# DCDC.net
KiCad netlist of a schematic drawn in Altium Designer
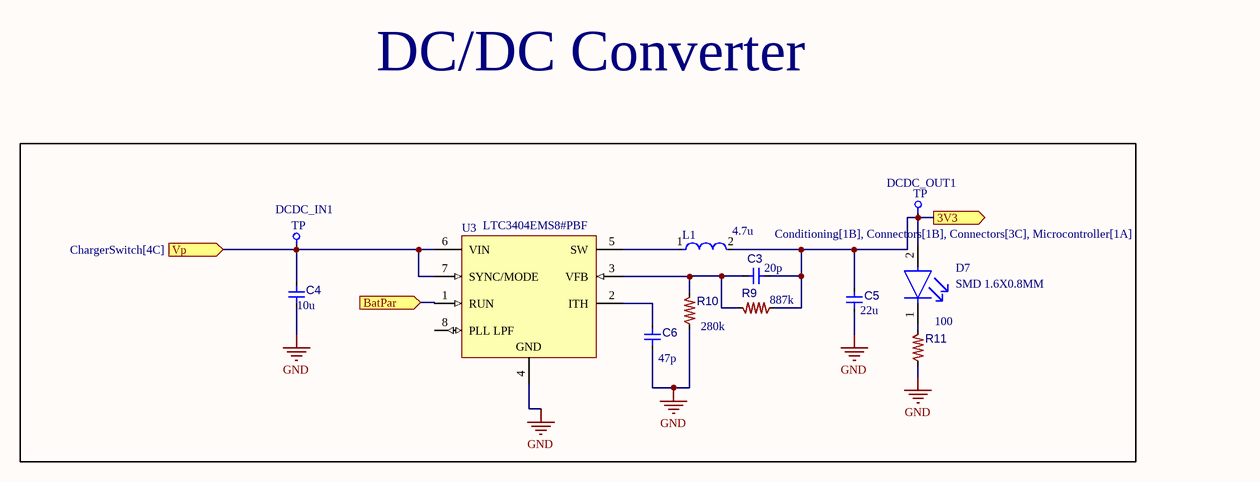
[diagram p0: DCDC.SchDoc]

(export (version "E")
  (design (tool "Eeschema 10.0.6"))
  (components
    (comp (ref "C3")
      (value "C63680")
      (footprint "New footprint 1")
      (description "200V 20pF C0G ±5% 0603 Multilayer Ceramic Capacitors MLCC - SMD/SMT ROHS")
      (libsource (lib "Muner") (part "CAP-NP-2"))
    )
    (comp (ref "C4")
      (value "C90806")
      (footprint "New footprint 1")
      (description "10V 10uF X5R ±10% 0603 Multilayer Ceramic Capacitors MLCC - SMD/SMT ROHS")
      (libsource (lib "Muner") (part "CAP-NP-2"))
    )
    (comp (ref "C5")
      (value "C93926")
      (footprint "New footprint 1")
      (description "6.3V 22uF X5R ±20% 0603 Multilayer Ceramic Capacitors MLCC - SMD/SMT ROHS")
      (libsource (lib "Muner") (part "CAP-NP-2"))
    )
    (comp (ref "C6")
      (value "C113801")
      (footprint "New footprint 1")
      (description "250V 47pF NP0 ±5% 0603 Multilayer Ceramic Capacitors MLCC - SMD/SMT ROHS")
      (libsource (lib "Muner") (part "CAP-NP-2"))
    )
    (comp (ref "D7")
      (value "SMD 1.6X0.8MM")
      (footprint "FP-APT1608LZGCK-MFG")
      (description "Standard LEDs - SMD 1.6X0.8MM LOW CRNT")
      (libsource (lib "Altium Content Vault") (part "8706943c75ba83719d021d2fdc84c58"))
    )
    (comp (ref "DCDC_IN1")
      (value "Test Pad")
      (footprint "Test Pad-Footprint-1")
      (libsource (lib "Muner") (part "Test Pad-Symbol-1"))
    )
    (comp (ref "DCDC_OUT1")
      (value "Test Pad")
      (footprint "Test Pad-Footprint-1")
      (libsource (lib "Muner") (part "Test Pad-Symbol-1"))
    )
    (comp (ref "L1")
      (value "C340379")
      (footprint "FP-SRN4018-MFG")
      (description "1.9A 4.7uH ±20% 2A SMD,4x4mm  Power Inductors ROHS")
      (fields
        (field (name "OCTOPART") "https://octopart.com/srn4018-4r7m-bourns-25452396")
        (field (name "TOLERANCE") "20%")
      )
      (libsource (lib "Altium Content Vault") (part "725321dda6339637d4d059423bc1c3c"))
    )
    (comp (ref "R9")
      (value "C403386")
      (footprint "0603 resistor-Footprint-1")
      (description "100mW Thick Film Resistors ±100ppm/℃ ±1% 887000Ω 0603 Chip Resistor - Surface Mount ROHS")
      (libsource (lib "Muner") (part "RES-2"))
    )
    (comp (ref "R10")
      (value "C100930")
      (footprint "0603 resistor-Footprint-1")
      (description "100mW Thick Film Resistors ±100ppm/℃ ±1% 280kΩ 0603 Chip Resistor - Surface Mount ROHS")
      (libsource (lib "Muner") (part "RES-2"))
    )
    (comp (ref "R11")
      (value "C176127")
      (footprint "0603 resistor-Footprint-1")
      (description "100mW Thick Film Resistors ±100ppm/℃ ±1% 100Ω 0603 Chip Resistor - Surface Mount ROHS")
      (libsource (lib "Muner") (part "RES-2"))
    )
    (comp (ref "U3")
      (value "LTC3404EMS8#PBF")
      (footprint "LT-MS8_L")
      (description "Step-down type Adjustable 600mA 2.65V~6V 0.8V~6V MSOP-8  DC-DC Converters ROHS")
      (fields (field (name "MANUFACTURER") "Linear Technology"))
      (libsource (lib "Altium Content Vault") (part "LT-LTC187X_3404-MS8-8"))
    )
  )
  (nets
    (net (code "1") (name "/3V3") (class "Default")
      (node (ref "C3") (pin "2") (pinfunction "2_2") (pintype "passive"))
      (node (ref "C5") (pin "2") (pinfunction "2_2") (pintype "passive"))
      (node (ref "D7") (pin "2") (pinfunction "A_2") (pintype "passive"))
      (node (ref "DCDC_OUT1") (pin "1") (pinfunction "1_1") (pintype "passive"))
      (node (ref "L1") (pin "2") (pinfunction "2_2") (pintype "passive"))
      (node (ref "R9") (pin "2") (pinfunction "2_2") (pintype "passive"))
    )
    (net (code "2") (name "/BatPar") (class "Default")
      (node (ref "U3") (pin "1") (pinfunction "RUN_1") (pintype "input"))
    )
    (net (code "3") (name "/Vp") (class "Default")
      (node (ref "C4") (pin "2") (pinfunction "2_2") (pintype "passive"))
      (node (ref "DCDC_IN1") (pin "1") (pinfunction "1_1") (pintype "passive"))
      (node (ref "U3") (pin "6") (pinfunction "VIN_6") (pintype "passive"))
      (node (ref "U3") (pin "7") (pinfunction "SYNC/MODE_7") (pintype "input"))
    )
    (net (code "4") (name "GND") (class "Default")
      (node (ref "C4") (pin "1") (pinfunction "1_1") (pintype "passive"))
      (node (ref "C5") (pin "1") (pinfunction "1_1") (pintype "passive"))
      (node (ref "C6") (pin "1") (pinfunction "1_1") (pintype "passive"))
      (node (ref "R10") (pin "2") (pinfunction "2_2") (pintype "passive"))
      (node (ref "R11") (pin "2") (pinfunction "2_2") (pintype "passive"))
      (node (ref "U3") (pin "4") (pinfunction "GND_4") (pintype "power_in"))
    )
    (net (code "5") (name "Net-(D7-C)") (class "Default")
      (node (ref "D7") (pin "1") (pinfunction "C_1") (pintype "passive"))
      (node (ref "R11") (pin "1") (pinfunction "1_1") (pintype "passive"))
    )
    (net (code "6") (name "Net-(U3-ITH)") (class "Default")
      (node (ref "C6") (pin "2") (pinfunction "2_2") (pintype "passive"))
      (node (ref "U3") (pin "2") (pinfunction "ITH_2") (pintype "passive"))
    )
    (net (code "7") (name "Net-(U3-SW)") (class "Default")
      (node (ref "L1") (pin "1") (pinfunction "1_1") (pintype "passive"))
      (node (ref "U3") (pin "5") (pinfunction "SW_5") (pintype "power_in"))
    )
    (net (code "8") (name "Net-(U3-VFB)") (class "Default")
      (node (ref "C3") (pin "1") (pinfunction "1_1") (pintype "passive"))
      (node (ref "R10") (pin "1") (pinfunction "1_1") (pintype "passive"))
      (node (ref "R9") (pin "1") (pinfunction "1_1") (pintype "passive"))
      (node (ref "U3") (pin "3") (pinfunction "VFB_3") (pintype "input"))
    )
    (net (code "9") (name "unconnected-(U3-PLL_LPF-Pad8)") (class "Default")
      (node (ref "U3") (pin "8") (pinfunction "PLL_LPF_8") (pintype "bidirectional"))
    )
  )
)
